# siren.net
KiCad netlist of a schematic drawn in EAGLE
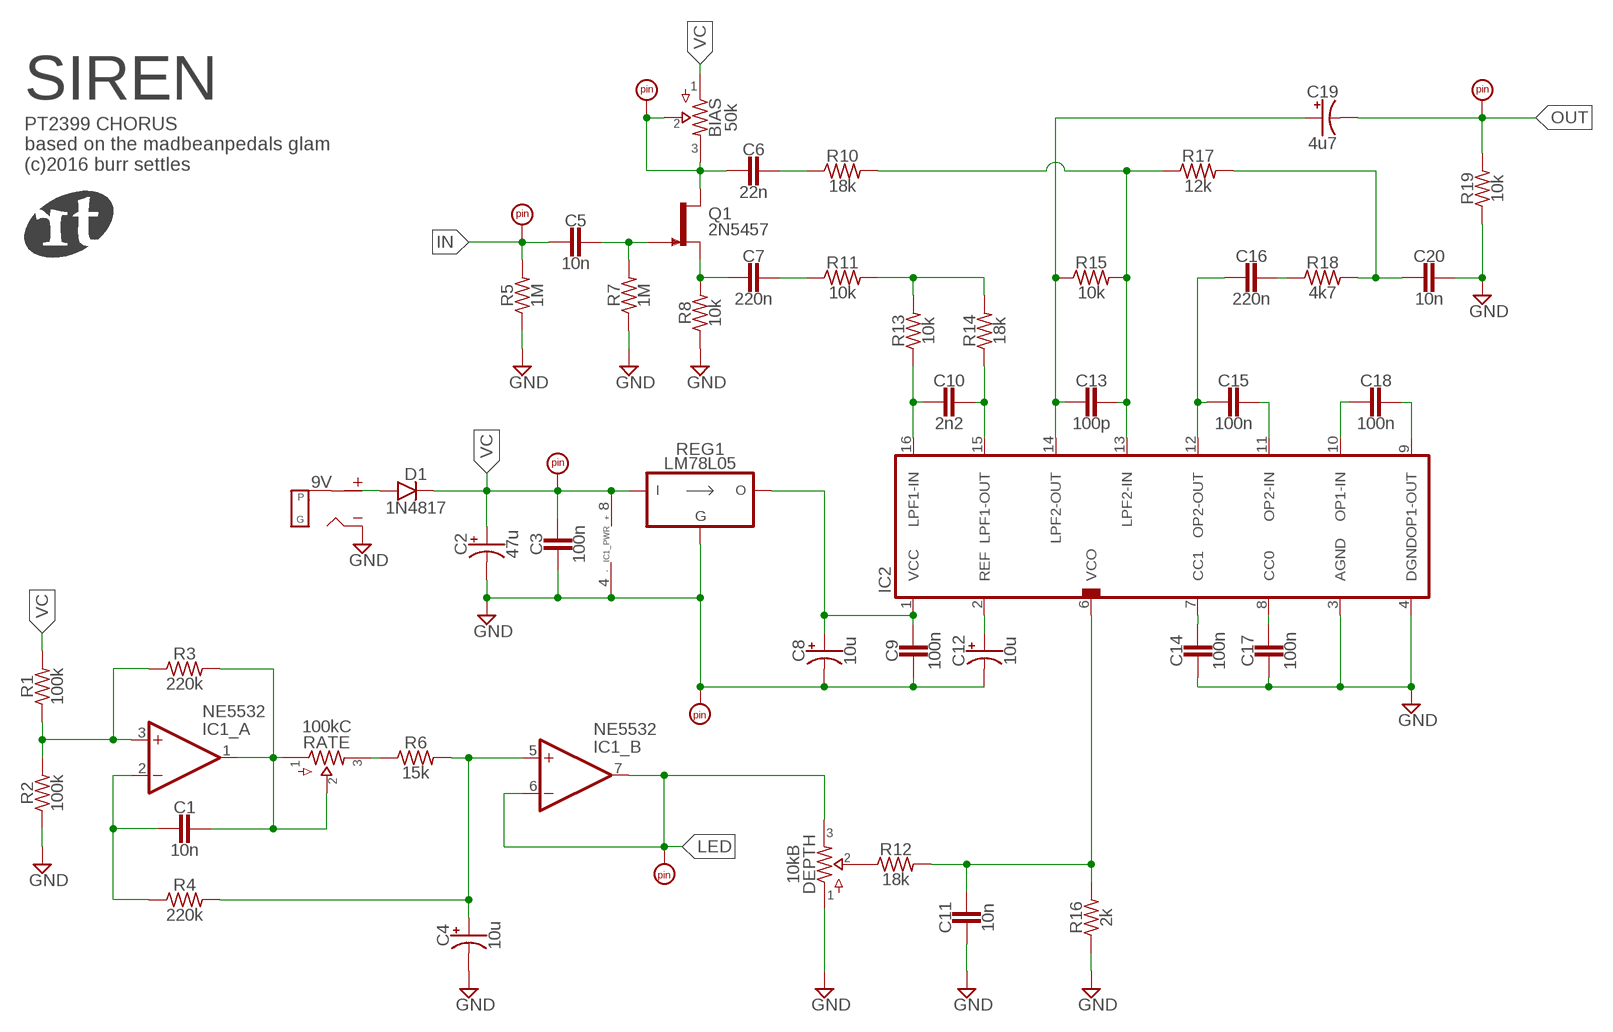
[diagram p0: schematic, sheet 1]

(export (version "E")
  (design (tool "Eeschema 10.0.6"))
  (components
    (comp (ref "9V")
      (value "DC_MONO")
      (footprint "eagle-import:DC")
      (libsource (lib "eagle-import") (part "DC_MONO"))
    )
    (comp (ref "BIAS")
      (value "50k")
      (footprint "eagle-import:2262_TRIM")
      (libsource (lib "eagle-import") (part "POTSTRIM"))
    )
    (comp (ref "C1")
      (value "10n")
      (footprint "eagle-import:050X030_025_2")
      (libsource (lib "eagle-import") (part "CER/FILM2"))
    )
    (comp (ref "C2")
      (value "47u")
      (footprint "eagle-import:050_020_1")
      (libsource (lib "eagle-import") (part "0501"))
    )
    (comp (ref "C3")
      (value "100n")
      (footprint "eagle-import:050X030_025_2")
      (libsource (lib "eagle-import") (part "CER/FILM2"))
    )
    (comp (ref "C4")
      (value "10u")
      (footprint "eagle-import:050_020_1")
      (libsource (lib "eagle-import") (part "0501"))
    )
    (comp (ref "C5")
      (value "10n")
      (footprint "eagle-import:050X030_025_2")
      (libsource (lib "eagle-import") (part "CER/FILM2"))
    )
    (comp (ref "C6")
      (value "22n")
      (footprint "eagle-import:050X030_025_2")
      (libsource (lib "eagle-import") (part "CER/FILM2"))
    )
    (comp (ref "C7")
      (value "220n")
      (footprint "eagle-import:050X030_025_2")
      (libsource (lib "eagle-import") (part "CER/FILM2"))
    )
    (comp (ref "C8")
      (value "10u")
      (footprint "eagle-import:050_020")
      (libsource (lib "eagle-import") (part "0500"))
    )
    (comp (ref "C9")
      (value "100n")
      (footprint "eagle-import:050X030_025_2")
      (libsource (lib "eagle-import") (part "CER/FILM2"))
    )
    (comp (ref "C10")
      (value "2n2")
      (footprint "eagle-import:050X030_025_2")
      (libsource (lib "eagle-import") (part "CER/FILM2"))
    )
    (comp (ref "C11")
      (value "10n")
      (footprint "eagle-import:050X030_025_2")
      (libsource (lib "eagle-import") (part "CER/FILM2"))
    )
    (comp (ref "C12")
      (value "10u")
      (footprint "eagle-import:050_020_1")
      (libsource (lib "eagle-import") (part "0501"))
    )
    (comp (ref "C13")
      (value "100p")
      (footprint "eagle-import:050X030_025_2")
      (libsource (lib "eagle-import") (part "CER/FILM2"))
    )
    (comp (ref "C14")
      (value "100n")
      (footprint "eagle-import:050X030_025_2")
      (libsource (lib "eagle-import") (part "CER/FILM2"))
    )
    (comp (ref "C15")
      (value "100n")
      (footprint "eagle-import:050X030_025_2")
      (libsource (lib "eagle-import") (part "CER/FILM2"))
    )
    (comp (ref "C16")
      (value "220n")
      (footprint "eagle-import:050X030_025_2")
      (libsource (lib "eagle-import") (part "CER/FILM2"))
    )
    (comp (ref "C17")
      (value "100n")
      (footprint "eagle-import:050X030_025_2")
      (libsource (lib "eagle-import") (part "CER/FILM2"))
    )
    (comp (ref "C18")
      (value "100n")
      (footprint "eagle-import:050X030_025_2")
      (libsource (lib "eagle-import") (part "CER/FILM2"))
    )
    (comp (ref "C19")
      (value "4u7")
      (footprint "eagle-import:050_020_1")
      (libsource (lib "eagle-import") (part "0501"))
    )
    (comp (ref "C20")
      (value "10n")
      (footprint "eagle-import:050X030_025_2")
      (libsource (lib "eagle-import") (part "CER/FILM2"))
    )
    (comp (ref "D1")
      (value "1N4817")
      (footprint "eagle-import:DO41-3")
      (libsource (lib "eagle-import") (part "DO41.3"))
    )
    (comp (ref "DEPTH")
      (value "10kB")
      (footprint "eagle-import:2262_TRIM")
      (libsource (lib "eagle-import") (part "POTSTRIM"))
    )
    (comp (ref "GND")
      (value "PADRND")
      (footprint "eagle-import:ROUND")
      (libsource (lib "eagle-import") (part "PADRND"))
    )
    (comp (ref "IC1")
      (value "NE5532")
      (footprint "eagle-import:DIL08")
      (libsource (lib "eagle-import") (part "DUALTH"))
    )
    (comp (ref "IC2")
      (value "PT2399TH")
      (footprint "eagle-import:DIL16")
      (libsource (lib "eagle-import") (part "PT2399TH"))
    )
    (comp (ref "IN")
      (value "PADSQR")
      (footprint "eagle-import:SQUARE")
      (libsource (lib "eagle-import") (part "PADSQR"))
    )
    (comp (ref "L+")
      (value "PADSQR")
      (footprint "eagle-import:SQUARE")
      (libsource (lib "eagle-import") (part "PADSQR"))
    )
    (comp (ref "OUT")
      (value "PADSQR")
      (footprint "eagle-import:SQUARE")
      (libsource (lib "eagle-import") (part "PADSQR"))
    )
    (comp (ref "PAD1")
      (value "PAD")
      (footprint "eagle-import:UNLABELED")
      (libsource (lib "eagle-import") (part "PAD"))
    )
    (comp (ref "PAD2")
      (value "PAD")
      (footprint "eagle-import:UNLABELED")
      (libsource (lib "eagle-import") (part "PAD"))
    )
    (comp (ref "Q1")
      (value "2N5457")
      (footprint "eagle-import:TO92-")
      (libsource (lib "eagle-import") (part "2N5457"))
    )
    (comp (ref "R1")
      (value "100k")
      (footprint "eagle-import:R0207_2V")
      (libsource (lib "eagle-import") (part "R_.2"))
    )
    (comp (ref "R2")
      (value "100k")
      (footprint "eagle-import:R0207_2V")
      (libsource (lib "eagle-import") (part "R_.2"))
    )
    (comp (ref "R3")
      (value "220k")
      (footprint "eagle-import:R0207_2V")
      (libsource (lib "eagle-import") (part "R_.2"))
    )
    (comp (ref "R4")
      (value "220k")
      (footprint "eagle-import:R0207_2V")
      (libsource (lib "eagle-import") (part "R_.2"))
    )
    (comp (ref "R5")
      (value "1M")
      (footprint "eagle-import:R0207_2V")
      (libsource (lib "eagle-import") (part "R_.2"))
    )
    (comp (ref "R6")
      (value "15k")
      (footprint "eagle-import:R0207_2V")
      (libsource (lib "eagle-import") (part "R_.2"))
    )
    (comp (ref "R7")
      (value "1M")
      (footprint "eagle-import:R0207_2V")
      (libsource (lib "eagle-import") (part "R_.2"))
    )
    (comp (ref "R8")
      (value "10k")
      (footprint "eagle-import:R0207_2V")
      (libsource (lib "eagle-import") (part "R_.2"))
    )
    (comp (ref "R10")
      (value "18k")
      (footprint "eagle-import:R0207_2V")
      (libsource (lib "eagle-import") (part "R_.2"))
    )
    (comp (ref "R11")
      (value "10k")
      (footprint "eagle-import:R0207_2V")
      (libsource (lib "eagle-import") (part "R_.2"))
    )
    (comp (ref "R12")
      (value "18k")
      (footprint "eagle-import:R0207_2V")
      (libsource (lib "eagle-import") (part "R_.2"))
    )
    (comp (ref "R13")
      (value "10k")
      (footprint "eagle-import:R0207_2V")
      (libsource (lib "eagle-import") (part "R_.2"))
    )
    (comp (ref "R14")
      (value "18k")
      (footprint "eagle-import:R0207_2V")
      (libsource (lib "eagle-import") (part "R_.2"))
    )
    (comp (ref "R15")
      (value "10k")
      (footprint "eagle-import:R0207_2V")
      (libsource (lib "eagle-import") (part "R_.2"))
    )
    (comp (ref "R16")
      (value "2k")
      (footprint "eagle-import:R0207_2V")
      (libsource (lib "eagle-import") (part "R_.2"))
    )
    (comp (ref "R17")
      (value "12k")
      (footprint "eagle-import:R0207_2V")
      (libsource (lib "eagle-import") (part "R_.2"))
    )
    (comp (ref "R18")
      (value "4k7")
      (footprint "eagle-import:R0207_2V")
      (libsource (lib "eagle-import") (part "R_.2"))
    )
    (comp (ref "R19")
      (value "10k")
      (footprint "eagle-import:R0207_2V")
      (libsource (lib "eagle-import") (part "R_.2"))
    )
    (comp (ref "RATE")
      (value "100kC")
      (footprint "eagle-import:PADS_SMALL")
      (libsource (lib "eagle-import") (part "POTSSMALL_PADS"))
    )
    (comp (ref "REG1")
      (value "LM78L05")
      (footprint "eagle-import:TO92-")
      (libsource (lib "eagle-import") (part "LM78L05"))
    )
  )
  (nets
    (net (code "1") (name "GND") (class "Default")
      (node (ref "9V") (pin "S") (pinfunction "SLEEVE_S") (pintype "passive"))
      (node (ref "C11") (pin "2") (pinfunction "2_2") (pintype "passive"))
      (node (ref "C12") (pin "-") (pinfunction "-_-") (pintype "passive"))
      (node (ref "C14") (pin "2") (pinfunction "2_2") (pintype "passive"))
      (node (ref "C17") (pin "2") (pinfunction "2_2") (pintype "passive"))
      (node (ref "C2") (pin "-") (pinfunction "-_-") (pintype "passive"))
      (node (ref "C20") (pin "1") (pinfunction "1_1") (pintype "passive"))
      (node (ref "C3") (pin "2") (pinfunction "2_2") (pintype "passive"))
      (node (ref "C4") (pin "-") (pinfunction "-_-") (pintype "passive"))
      (node (ref "C8") (pin "-") (pinfunction "-_-") (pintype "passive"))
      (node (ref "C9") (pin "2") (pinfunction "2_2") (pintype "passive"))
      (node (ref "DEPTH") (pin "1") (pinfunction "1_1") (pintype "passive"))
      (node (ref "GND") (pin "1") (pinfunction "P$1_1") (pintype "bidirectional"))
      (node (ref "IC1") (pin "4") (pinfunction "V-_4") (pintype "power_in"))
      (node (ref "IC2") (pin "3") (pinfunction "AGND_3") (pintype "power_in"))
      (node (ref "IC2") (pin "4") (pinfunction "DGND_4") (pintype "power_in"))
      (node (ref "R16") (pin "1") (pinfunction "1_1") (pintype "passive"))
      (node (ref "R19") (pin "1") (pinfunction "1_1") (pintype "passive"))
      (node (ref "R2") (pin "1") (pinfunction "1_1") (pintype "passive"))
      (node (ref "R5") (pin "1") (pinfunction "1_1") (pintype "passive"))
      (node (ref "R7") (pin "1") (pinfunction "1_1") (pintype "passive"))
      (node (ref "R8") (pin "1") (pinfunction "1_1") (pintype "passive"))
      (node (ref "REG1") (pin "2") (pinfunction "GND_2") (pintype "passive"))
    )
    (net (code "2") (name "IN") (class "Default")
      (node (ref "C5") (pin "2") (pinfunction "2_2") (pintype "passive"))
      (node (ref "IN") (pin "1") (pinfunction "P$1_1") (pintype "bidirectional"))
      (node (ref "R5") (pin "2") (pinfunction "2_2") (pintype "passive"))
    )
    (net (code "3") (name "LED") (class "Default")
      (node (ref "DEPTH") (pin "3") (pinfunction "3_3") (pintype "passive"))
      (node (ref "IC1") (pin "6") (pinfunction "-IN_6") (pintype "input"))
      (node (ref "IC1") (pin "7") (pinfunction "OUT_7") (pintype "output"))
      (node (ref "L+") (pin "1") (pinfunction "P$1_1") (pintype "bidirectional"))
    )
    (net (code "4") (name "Net-(9V-TIP)") (class "Default")
      (node (ref "9V") (pin "T") (pinfunction "TIP_T") (pintype "passive"))
      (node (ref "D1") (pin "A") (pinfunction "A_A") (pintype "passive"))
    )
    (net (code "5") (name "Net-(C6-Pad1)") (class "Default")
      (node (ref "C6") (pin "1") (pinfunction "1_1") (pintype "passive"))
      (node (ref "R10") (pin "1") (pinfunction "1_1") (pintype "passive"))
    )
    (net (code "6") (name "Net-(C7-Pad1)") (class "Default")
      (node (ref "C7") (pin "1") (pinfunction "1_1") (pintype "passive"))
      (node (ref "R11") (pin "1") (pinfunction "1_1") (pintype "passive"))
    )
    (net (code "7") (name "Net-(C16-Pad1)") (class "Default")
      (node (ref "C16") (pin "1") (pinfunction "1_1") (pintype "passive"))
      (node (ref "R18") (pin "1") (pinfunction "1_1") (pintype "passive"))
    )
    (net (code "8") (name "Net-(C20-Pad2)") (class "Default")
      (node (ref "C20") (pin "2") (pinfunction "2_2") (pintype "passive"))
      (node (ref "R17") (pin "2") (pinfunction "2_2") (pintype "passive"))
      (node (ref "R18") (pin "2") (pinfunction "2_2") (pintype "passive"))
    )
    (net (code "9") (name "Net-(DEPTH-Pad2)") (class "Default")
      (node (ref "DEPTH") (pin "2") (pinfunction "2_2") (pintype "passive"))
      (node (ref "R12") (pin "1") (pinfunction "1_1") (pintype "passive"))
    )
    (net (code "10") (name "Net-(IC1A-+IN)") (class "Default")
      (node (ref "IC1") (pin "3") (pinfunction "+IN_3") (pintype "input"))
      (node (ref "R1") (pin "1") (pinfunction "1_1") (pintype "passive"))
      (node (ref "R2") (pin "2") (pinfunction "2_2") (pintype "passive"))
      (node (ref "R3") (pin "1") (pinfunction "1_1") (pintype "passive"))
    )
    (net (code "11") (name "Net-(IC1A--IN)") (class "Default")
      (node (ref "C1") (pin "2") (pinfunction "2_2") (pintype "passive"))
      (node (ref "IC1") (pin "2") (pinfunction "-IN_2") (pintype "input"))
      (node (ref "R4") (pin "1") (pinfunction "1_1") (pintype "passive"))
    )
    (net (code "12") (name "Net-(IC1A-OUT)") (class "Default")
      (node (ref "C1") (pin "1") (pinfunction "1_1") (pintype "passive"))
      (node (ref "IC1") (pin "1") (pinfunction "OUT_1") (pintype "output"))
      (node (ref "R3") (pin "2") (pinfunction "2_2") (pintype "passive"))
      (node (ref "RATE") (pin "1") (pinfunction "1_1") (pintype "passive"))
      (node (ref "RATE") (pin "2") (pinfunction "2_2") (pintype "passive"))
    )
    (net (code "13") (name "Net-(IC1B-+IN)") (class "Default")
      (node (ref "C4") (pin "+") (pinfunction "+_+") (pintype "passive"))
      (node (ref "IC1") (pin "5") (pinfunction "+IN_5") (pintype "input"))
      (node (ref "R4") (pin "2") (pinfunction "2_2") (pintype "passive"))
      (node (ref "R6") (pin "2") (pinfunction "2_2") (pintype "passive"))
    )
    (net (code "14") (name "Net-(IC2-CC0)") (class "Default")
      (node (ref "C17") (pin "1") (pinfunction "1_1") (pintype "passive"))
      (node (ref "IC2") (pin "8") (pinfunction "CC0_8") (pintype "input"))
    )
    (net (code "15") (name "Net-(IC2-CC1)") (class "Default")
      (node (ref "C14") (pin "1") (pinfunction "1_1") (pintype "passive"))
      (node (ref "IC2") (pin "7") (pinfunction "CC1_7") (pintype "input"))
    )
    (net (code "16") (name "Net-(IC2-LPF1-IN)") (class "Default")
      (node (ref "C10") (pin "2") (pinfunction "2_2") (pintype "passive"))
      (node (ref "IC2") (pin "16") (pinfunction "LPF1-IN_16") (pintype "input"))
      (node (ref "R13") (pin "1") (pinfunction "1_1") (pintype "passive"))
    )
    (net (code "17") (name "Net-(IC2-LPF1-OUT)") (class "Default")
      (node (ref "C10") (pin "1") (pinfunction "1_1") (pintype "passive"))
      (node (ref "IC2") (pin "15") (pinfunction "LPF1-OUT_15") (pintype "output"))
      (node (ref "R14") (pin "1") (pinfunction "1_1") (pintype "passive"))
    )
    (net (code "18") (name "Net-(IC2-LPF2-IN)") (class "Default")
      (node (ref "C13") (pin "1") (pinfunction "1_1") (pintype "passive"))
      (node (ref "IC2") (pin "13") (pinfunction "LPF2-IN_13") (pintype "input"))
      (node (ref "R10") (pin "2") (pinfunction "2_2") (pintype "passive"))
      (node (ref "R15") (pin "2") (pinfunction "2_2") (pintype "passive"))
      (node (ref "R17") (pin "1") (pinfunction "1_1") (pintype "passive"))
    )
    (net (code "19") (name "Net-(IC2-LPF2-OUT)") (class "Default")
      (node (ref "C13") (pin "2") (pinfunction "2_2") (pintype "passive"))
      (node (ref "C19") (pin "+") (pinfunction "+_+") (pintype "passive"))
      (node (ref "IC2") (pin "14") (pinfunction "LPF2-OUT_14") (pintype "output"))
      (node (ref "R15") (pin "1") (pinfunction "1_1") (pintype "passive"))
    )
    (net (code "20") (name "Net-(IC2-OP1-IN)") (class "Default")
      (node (ref "C18") (pin "2") (pinfunction "2_2") (pintype "passive"))
      (node (ref "IC2") (pin "10") (pinfunction "OP1-IN_10") (pintype "input"))
    )
    (net (code "21") (name "Net-(IC2-OP1-OUT)") (class "Default")
      (node (ref "C18") (pin "1") (pinfunction "1_1") (pintype "passive"))
      (node (ref "IC2") (pin "9") (pinfunction "OP1-OUT_9") (pintype "output"))
    )
    (net (code "22") (name "Net-(IC2-OP2-IN)") (class "Default")
      (node (ref "C15") (pin "1") (pinfunction "1_1") (pintype "passive"))
      (node (ref "IC2") (pin "11") (pinfunction "OP2-IN_11") (pintype "input"))
    )
    (net (code "23") (name "Net-(IC2-OP2-OUT)") (class "Default")
      (node (ref "C15") (pin "2") (pinfunction "2_2") (pintype "passive"))
      (node (ref "C16") (pin "2") (pinfunction "2_2") (pintype "passive"))
      (node (ref "IC2") (pin "12") (pinfunction "OP2-OUT_12") (pintype "output"))
    )
    (net (code "24") (name "Net-(IC2-REF)") (class "Default")
      (node (ref "C12") (pin "+") (pinfunction "+_+") (pintype "passive"))
      (node (ref "IC2") (pin "2") (pinfunction "REF_2") (pintype "input"))
    )
    (net (code "25") (name "Net-(IC2-VCC)") (class "Default")
      (node (ref "C8") (pin "+") (pinfunction "+_+") (pintype "passive"))
      (node (ref "C9") (pin "1") (pinfunction "1_1") (pintype "passive"))
      (node (ref "IC2") (pin "1") (pinfunction "VCC_1") (pintype "power_in"))
      (node (ref "REG1") (pin "3") (pinfunction "VO_3") (pintype "passive"))
    )
    (net (code "26") (name "Net-(IC2-VCO)") (class "Default")
      (node (ref "C11") (pin "1") (pinfunction "1_1") (pintype "passive"))
      (node (ref "IC2") (pin "6") (pinfunction "VCO_6") (pintype "input"))
      (node (ref "R12") (pin "2") (pinfunction "2_2") (pintype "passive"))
      (node (ref "R16") (pin "2") (pinfunction "2_2") (pintype "passive"))
    )
    (net (code "27") (name "Net-(Q1-D)") (class "Default")
      (node (ref "BIAS") (pin "2") (pinfunction "2_2") (pintype "passive"))
      (node (ref "BIAS") (pin "3") (pinfunction "3_3") (pintype "passive"))
      (node (ref "C6") (pin "2") (pinfunction "2_2") (pintype "passive"))
      (node (ref "PAD2") (pin "P$1") (pinfunction "P$1_P$1") (pintype "bidirectional"))
      (node (ref "Q1") (pin "3") (pinfunction "D_3") (pintype "passive"))
    )
    (net (code "28") (name "Net-(Q1-G)") (class "Default")
      (node (ref "C5") (pin "1") (pinfunction "1_1") (pintype "passive"))
      (node (ref "Q1") (pin "1") (pinfunction "G_1") (pintype "passive"))
      (node (ref "R7") (pin "2") (pinfunction "2_2") (pintype "passive"))
    )
    (net (code "29") (name "Net-(Q1-S)") (class "Default")
      (node (ref "C7") (pin "2") (pinfunction "2_2") (pintype "passive"))
      (node (ref "Q1") (pin "2") (pinfunction "S_2") (pintype "passive"))
      (node (ref "R8") (pin "2") (pinfunction "2_2") (pintype "passive"))
    )
    (net (code "30") (name "Net-(R6-Pad1)") (class "Default")
      (node (ref "R6") (pin "1") (pinfunction "1_1") (pintype "passive"))
      (node (ref "RATE") (pin "3") (pinfunction "3_3") (pintype "passive"))
    )
    (net (code "31") (name "Net-(R11-Pad2)") (class "Default")
      (node (ref "R11") (pin "2") (pinfunction "2_2") (pintype "passive"))
      (node (ref "R13") (pin "2") (pinfunction "2_2") (pintype "passive"))
      (node (ref "R14") (pin "2") (pinfunction "2_2") (pintype "passive"))
    )
    (net (code "32") (name "OUT") (class "Default")
      (node (ref "C19") (pin "-") (pinfunction "-_-") (pintype "passive"))
      (node (ref "OUT") (pin "1") (pinfunction "P$1_1") (pintype "bidirectional"))
      (node (ref "R19") (pin "2") (pinfunction "2_2") (pintype "passive"))
    )
    (net (code "33") (name "VC") (class "Default")
      (node (ref "BIAS") (pin "1") (pinfunction "1_1") (pintype "passive"))
      (node (ref "C2") (pin "+") (pinfunction "+_+") (pintype "passive"))
      (node (ref "C3") (pin "1") (pinfunction "1_1") (pintype "passive"))
      (node (ref "D1") (pin "C") (pinfunction "C_C") (pintype "passive"))
      (node (ref "IC1") (pin "8") (pinfunction "V+_8") (pintype "power_in"))
      (node (ref "PAD1") (pin "P$1") (pinfunction "P$1_P$1") (pintype "bidirectional"))
      (node (ref "R1") (pin "2") (pinfunction "2_2") (pintype "passive"))
      (node (ref "REG1") (pin "1") (pinfunction "VI_1") (pintype "input"))
    )
  )
)
